# design.net
KiCad netlist of a schematic drawn in Altium Designer
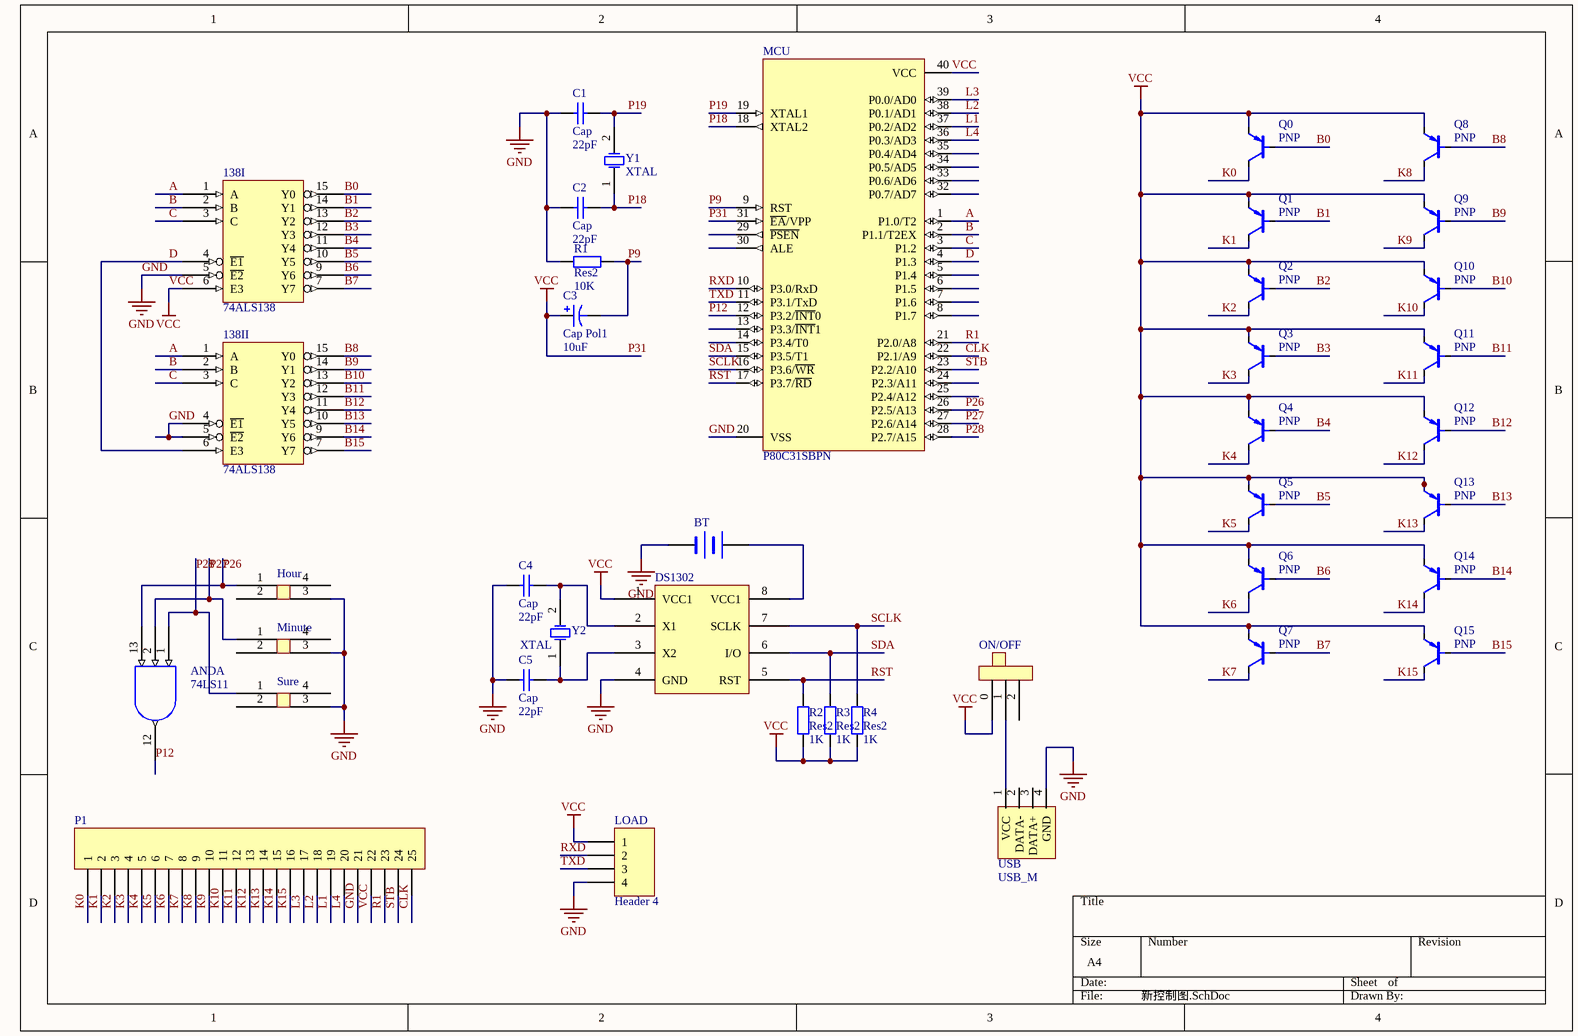
[diagram p0: 新控制图.SchDoc]

(export (version "E")
  (design (tool "Eeschema 10.0.6"))
  (components
    (comp (ref "138I")
      (value "74ALS138")
      (footprint "DIP-16")
      (libsource (lib "TTL74系列IC") (part "74ALS138"))
    )
    (comp (ref "138II")
      (value "74ALS138")
      (footprint "DIP-16")
      (libsource (lib "TTL74系列IC") (part "74ALS138"))
    )
    (comp (ref "AND") (value "74LS11") (footprint "DIP-14") (libsource (lib "TTL74系列IC") (part "74LS11")))
    (comp (ref "BT")
      (value "~")
      (footprint "纽扣电池:PCBComponent_1")
      (description "Battery")
      (libsource (lib "电池及电源") (part "干电池"))
    )
    (comp (ref "C1")
      (value "Cap")
      (footprint "Miscellaneous Connectors:HDR1X2")
      (description "Capacitor")
      (fields (field (name "ALTIUM_VALUE") "22pF") (field (name "PUBLISHER") "Altium Limited"))
      (libsource (lib "Miscellaneous Devices") (part "Cap"))
    )
    (comp (ref "C2")
      (value "Cap")
      (footprint "Miscellaneous Connectors:HDR1X2")
      (description "Capacitor")
      (fields (field (name "ALTIUM_VALUE") "22pF") (field (name "PUBLISHER") "Altium Limited"))
      (libsource (lib "Miscellaneous Devices") (part "Cap"))
    )
    (comp (ref "C3")
      (value "Cap Pol1")
      (footprint "单片机最小系统:LED")
      (description "Polarized Capacitor (Radial)")
      (fields (field (name "ALTIUM_VALUE") "10uF") (field (name "PUBLISHER") "Altium Limited"))
      (libsource (lib "Miscellaneous Devices") (part "Cap Pol1"))
    )
    (comp (ref "C4")
      (value "Cap")
      (footprint "PIN2")
      (description "Capacitor")
      (fields (field (name "ALTIUM_VALUE") "22pF") (field (name "PUBLISHER") "Altium Limited"))
      (libsource (lib "Miscellaneous Devices") (part "Cap"))
    )
    (comp (ref "C5")
      (value "Cap")
      (footprint "PIN2")
      (description "Capacitor")
      (fields (field (name "ALTIUM_VALUE") "22pF") (field (name "PUBLISHER") "Altium Limited"))
      (libsource (lib "Miscellaneous Devices") (part "Cap"))
    )
    (comp (ref "DS1302") (value "~") (footprint "DIP8") (libsource (lib "DS1302") (part "Component_1")))
    (comp (ref "Hour")
      (value "~")
      (footprint "立式按键:PCBComponent_1")
      (libsource (lib "按键1") (part "Component_1"))
    )
    (comp (ref "LOAD")
      (value "Header 4")
      (footprint "HDR1X4")
      (description "Header, 4-Pin")
      (fields (field (name "PUBLISHER") "Altium Limited"))
      (libsource (lib "Miscellaneous Connectors") (part "Header 4"))
    )
    (comp (ref "MCU")
      (value "P80C31SBPN")
      (footprint "SOT129-1")
      (description "80C51 8-Bit Microcontroller Family: 128 B RAM, ROMless, 2.7 V-5.5 V, Low Power, High Speed")
      (fields (field (name "PUBLISHER") "Altium Limited"))
      (libsource (lib "Philips Microcontroller 8-Bit") (part "P80C31SBPN"))
    )
    (comp (ref "Minute")
      (value "~")
      (footprint "立式按键:PCBComponent_1")
      (libsource (lib "按键1") (part "Component_1"))
    )
    (comp (ref "ON/OFF")
      (value "~")
      (footprint "新开关:PCBComponent_1")
      (libsource (lib "新开关") (part "Component_1"))
    )
    (comp (ref "P1")
      (value "~")
      (footprint "HDR1X25")
      (description "Header, 25-Pin")
      (fields (field (name "PUBLISHER") "Altium Limited"))
      (libsource (lib "Miscellaneous Connectors") (part "Header 25"))
    )
    (comp (ref "Q0") (value "PNP") (footprint "TO-92") (libsource (lib "常用元件库") (part "PNP")))
    (comp (ref "Q1") (value "PNP") (footprint "TO-92") (libsource (lib "常用元件库") (part "PNP")))
    (comp (ref "Q2") (value "PNP") (footprint "TO-92") (libsource (lib "常用元件库") (part "PNP")))
    (comp (ref "Q3") (value "PNP") (footprint "TO-92") (libsource (lib "常用元件库") (part "PNP")))
    (comp (ref "Q4") (value "PNP") (footprint "TO-92") (libsource (lib "常用元件库") (part "PNP")))
    (comp (ref "Q5") (value "PNP") (footprint "TO-92") (libsource (lib "常用元件库") (part "PNP")))
    (comp (ref "Q6") (value "PNP") (footprint "TO-92") (libsource (lib "常用元件库") (part "PNP")))
    (comp (ref "Q7") (value "PNP") (footprint "TO-92") (libsource (lib "常用元件库") (part "PNP")))
    (comp (ref "Q8") (value "PNP") (footprint "TO-92") (libsource (lib "常用元件库") (part "PNP")))
    (comp (ref "Q9") (value "PNP") (footprint "TO-92") (libsource (lib "常用元件库") (part "PNP")))
    (comp (ref "Q10") (value "PNP") (footprint "TO-92") (libsource (lib "常用元件库") (part "PNP")))
    (comp (ref "Q11") (value "PNP") (footprint "TO-92") (libsource (lib "常用元件库") (part "PNP")))
    (comp (ref "Q12") (value "PNP") (footprint "TO-92") (libsource (lib "常用元件库") (part "PNP")))
    (comp (ref "Q13") (value "PNP") (footprint "TO-92") (libsource (lib "常用元件库") (part "PNP")))
    (comp (ref "Q14") (value "PNP") (footprint "TO-92") (libsource (lib "常用元件库") (part "PNP")))
    (comp (ref "Q15") (value "PNP") (footprint "TO-92") (libsource (lib "常用元件库") (part "PNP")))
    (comp (ref "R1")
      (value "Res2")
      (footprint "AXIAL-0.4")
      (description "Resistor")
      (fields (field (name "ALTIUM_VALUE") "10K") (field (name "PUBLISHER") "Altium Limited"))
      (libsource (lib "Miscellaneous Devices") (part "Res2"))
    )
    (comp (ref "R2")
      (value "Res2")
      (footprint "AXIAL-0.4")
      (description "Resistor")
      (fields (field (name "ALTIUM_VALUE") "1K") (field (name "PUBLISHER") "Altium Limited"))
      (libsource (lib "") (part "Res2_1"))
    )
    (comp (ref "R3")
      (value "Res2")
      (footprint "AXIAL-0.4")
      (description "Resistor")
      (fields (field (name "ALTIUM_VALUE") "1K") (field (name "PUBLISHER") "Altium Limited"))
      (libsource (lib "") (part "Res2_1"))
    )
    (comp (ref "R4")
      (value "Res2")
      (footprint "AXIAL-0.4")
      (description "Resistor")
      (fields (field (name "ALTIUM_VALUE") "1K") (field (name "PUBLISHER") "Altium Limited"))
      (libsource (lib "") (part "Res2_1"))
    )
    (comp (ref "Sure")
      (value "~")
      (footprint "立式按键:PCBComponent_1")
      (libsource (lib "按键1") (part "Component_1"))
    )
    (comp (ref "USB") (value "USB_M") (footprint "USB") (libsource (lib "SCH封装库") (part "USB_M")))
    (comp (ref "Y1")
      (value "XTAL")
      (footprint "晶振:PCBComponent_1")
      (description "Crystal Oscillator")
      (fields (field (name "PUBLISHER") "Altium Limited"))
      (libsource (lib "Miscellaneous Devices") (part "XTAL"))
    )
    (comp (ref "Y2")
      (value "XTAL")
      (footprint "HDR1X2")
      (description "Crystal Oscillator")
      (fields (field (name "PUBLISHER") "Altium Limited"))
      (libsource (lib "Miscellaneous Devices") (part "XTAL"))
    )
  )
  (nets
    (net (code "1") (name "/A") (class "Default")
      (node (ref "138I") (pin "1") (pinfunction "A_1") (pintype "input"))
      (node (ref "138II") (pin "1") (pinfunction "A_1") (pintype "input"))
      (node (ref "MCU") (pin "1") (pinfunction "P1.0/T2_1") (pintype "bidirectional"))
    )
    (net (code "2") (name "/B") (class "Default")
      (node (ref "138I") (pin "2") (pinfunction "B_2") (pintype "input"))
      (node (ref "138II") (pin "2") (pinfunction "B_2") (pintype "input"))
      (node (ref "MCU") (pin "2") (pinfunction "P1.1/T2EX_2") (pintype "bidirectional"))
    )
    (net (code "3") (name "/B0") (class "Default")
      (node (ref "138I") (pin "15") (pinfunction "Y0_15") (pintype "output"))
      (node (ref "Q0") (pin "B") (pinfunction "b_B") (pintype "passive"))
    )
    (net (code "4") (name "/B1") (class "Default")
      (node (ref "138I") (pin "14") (pinfunction "Y1_14") (pintype "output"))
      (node (ref "Q1") (pin "B") (pinfunction "b_B") (pintype "passive"))
    )
    (net (code "5") (name "/B2") (class "Default")
      (node (ref "138I") (pin "13") (pinfunction "Y2_13") (pintype "output"))
      (node (ref "Q2") (pin "B") (pinfunction "b_B") (pintype "passive"))
    )
    (net (code "6") (name "/B3") (class "Default")
      (node (ref "138I") (pin "12") (pinfunction "Y3_12") (pintype "output"))
      (node (ref "Q3") (pin "B") (pinfunction "b_B") (pintype "passive"))
    )
    (net (code "7") (name "/B4") (class "Default")
      (node (ref "138I") (pin "11") (pinfunction "Y4_11") (pintype "output"))
      (node (ref "Q4") (pin "B") (pinfunction "b_B") (pintype "passive"))
    )
    (net (code "8") (name "/B5") (class "Default")
      (node (ref "138I") (pin "10") (pinfunction "Y5_10") (pintype "output"))
      (node (ref "Q5") (pin "B") (pinfunction "b_B") (pintype "passive"))
    )
    (net (code "9") (name "/B6") (class "Default")
      (node (ref "138I") (pin "9") (pinfunction "Y6_9") (pintype "output"))
      (node (ref "Q6") (pin "B") (pinfunction "b_B") (pintype "passive"))
    )
    (net (code "10") (name "/B7") (class "Default")
      (node (ref "138I") (pin "7") (pinfunction "Y7_7") (pintype "output"))
      (node (ref "Q7") (pin "B") (pinfunction "b_B") (pintype "passive"))
    )
    (net (code "11") (name "/B8") (class "Default")
      (node (ref "138II") (pin "15") (pinfunction "Y0_15") (pintype "output"))
      (node (ref "Q8") (pin "B") (pinfunction "b_B") (pintype "passive"))
    )
    (net (code "12") (name "/B9") (class "Default")
      (node (ref "138II") (pin "14") (pinfunction "Y1_14") (pintype "output"))
      (node (ref "Q9") (pin "B") (pinfunction "b_B") (pintype "passive"))
    )
    (net (code "13") (name "/B10") (class "Default")
      (node (ref "138II") (pin "13") (pinfunction "Y2_13") (pintype "output"))
      (node (ref "Q10") (pin "B") (pinfunction "b_B") (pintype "passive"))
    )
    (net (code "14") (name "/B11") (class "Default")
      (node (ref "138II") (pin "12") (pinfunction "Y3_12") (pintype "output"))
      (node (ref "Q11") (pin "B") (pinfunction "b_B") (pintype "passive"))
    )
    (net (code "15") (name "/B12") (class "Default")
      (node (ref "138II") (pin "11") (pinfunction "Y4_11") (pintype "output"))
      (node (ref "Q12") (pin "B") (pinfunction "b_B") (pintype "passive"))
    )
    (net (code "16") (name "/B13") (class "Default")
      (node (ref "138II") (pin "10") (pinfunction "Y5_10") (pintype "output"))
      (node (ref "Q13") (pin "B") (pinfunction "b_B") (pintype "passive"))
    )
    (net (code "17") (name "/B14") (class "Default")
      (node (ref "138II") (pin "9") (pinfunction "Y6_9") (pintype "output"))
      (node (ref "Q14") (pin "B") (pinfunction "b_B") (pintype "passive"))
    )
    (net (code "18") (name "/B15") (class "Default")
      (node (ref "138II") (pin "7") (pinfunction "Y7_7") (pintype "output"))
      (node (ref "Q15") (pin "B") (pinfunction "b_B") (pintype "passive"))
    )
    (net (code "19") (name "/C") (class "Default")
      (node (ref "138I") (pin "3") (pinfunction "C_3") (pintype "input"))
      (node (ref "138II") (pin "3") (pinfunction "C_3") (pintype "input"))
      (node (ref "MCU") (pin "3") (pinfunction "P1.2_3") (pintype "bidirectional"))
    )
    (net (code "20") (name "/CLK") (class "Default")
      (node (ref "MCU") (pin "22") (pinfunction "P2.1/A9_22") (pintype "bidirectional"))
      (node (ref "P1") (pin "25") (pinfunction "25_25") (pintype "passive"))
    )
    (net (code "21") (name "/D") (class "Default")
      (node (ref "138I") (pin "4") (pinfunction "~{E1}_4") (pintype "input"))
      (node (ref "138II") (pin "6") (pinfunction "E3_6") (pintype "input"))
      (node (ref "MCU") (pin "4") (pinfunction "P1.3_4") (pintype "bidirectional"))
    )
    (net (code "22") (name "/K0") (class "Default")
      (node (ref "P1") (pin "1") (pinfunction "1_1") (pintype "passive"))
      (node (ref "Q0") (pin "C") (pinfunction "c_C") (pintype "passive"))
    )
    (net (code "23") (name "/K1") (class "Default")
      (node (ref "P1") (pin "2") (pinfunction "2_2") (pintype "passive"))
      (node (ref "Q1") (pin "C") (pinfunction "c_C") (pintype "passive"))
    )
    (net (code "24") (name "/K2") (class "Default")
      (node (ref "P1") (pin "3") (pinfunction "3_3") (pintype "passive"))
      (node (ref "Q2") (pin "C") (pinfunction "c_C") (pintype "passive"))
    )
    (net (code "25") (name "/K3") (class "Default")
      (node (ref "P1") (pin "4") (pinfunction "4_4") (pintype "passive"))
      (node (ref "Q3") (pin "C") (pinfunction "c_C") (pintype "passive"))
    )
    (net (code "26") (name "/K4") (class "Default")
      (node (ref "P1") (pin "5") (pinfunction "5_5") (pintype "passive"))
      (node (ref "Q4") (pin "C") (pinfunction "c_C") (pintype "passive"))
    )
    (net (code "27") (name "/K5") (class "Default")
      (node (ref "P1") (pin "6") (pinfunction "6_6") (pintype "passive"))
      (node (ref "Q5") (pin "C") (pinfunction "c_C") (pintype "passive"))
    )
    (net (code "28") (name "/K6") (class "Default")
      (node (ref "P1") (pin "7") (pinfunction "7_7") (pintype "passive"))
      (node (ref "Q6") (pin "C") (pinfunction "c_C") (pintype "passive"))
    )
    (net (code "29") (name "/K7") (class "Default")
      (node (ref "P1") (pin "8") (pinfunction "8_8") (pintype "passive"))
      (node (ref "Q7") (pin "C") (pinfunction "c_C") (pintype "passive"))
    )
    (net (code "30") (name "/K8") (class "Default")
      (node (ref "P1") (pin "9") (pinfunction "9_9") (pintype "passive"))
      (node (ref "Q8") (pin "C") (pinfunction "c_C") (pintype "passive"))
    )
    (net (code "31") (name "/K9") (class "Default")
      (node (ref "P1") (pin "10") (pinfunction "10_10") (pintype "passive"))
      (node (ref "Q9") (pin "C") (pinfunction "c_C") (pintype "passive"))
    )
    (net (code "32") (name "/K10") (class "Default")
      (node (ref "P1") (pin "11") (pinfunction "11_11") (pintype "passive"))
      (node (ref "Q10") (pin "C") (pinfunction "c_C") (pintype "passive"))
    )
    (net (code "33") (name "/K11") (class "Default")
      (node (ref "P1") (pin "12") (pinfunction "12_12") (pintype "passive"))
      (node (ref "Q11") (pin "C") (pinfunction "c_C") (pintype "passive"))
    )
    (net (code "34") (name "/K12") (class "Default")
      (node (ref "P1") (pin "13") (pinfunction "13_13") (pintype "passive"))
      (node (ref "Q12") (pin "C") (pinfunction "c_C") (pintype "passive"))
    )
    (net (code "35") (name "/K13") (class "Default")
      (node (ref "P1") (pin "14") (pinfunction "14_14") (pintype "passive"))
      (node (ref "Q13") (pin "C") (pinfunction "c_C") (pintype "passive"))
    )
    (net (code "36") (name "/K14") (class "Default")
      (node (ref "P1") (pin "15") (pinfunction "15_15") (pintype "passive"))
      (node (ref "Q14") (pin "C") (pinfunction "c_C") (pintype "passive"))
    )
    (net (code "37") (name "/K15") (class "Default")
      (node (ref "P1") (pin "16") (pinfunction "16_16") (pintype "passive"))
      (node (ref "Q15") (pin "C") (pinfunction "c_C") (pintype "passive"))
    )
    (net (code "38") (name "/L1") (class "Default")
      (node (ref "MCU") (pin "37") (pinfunction "P0.2/AD2_37") (pintype "bidirectional"))
      (node (ref "P1") (pin "19") (pinfunction "19_19") (pintype "passive"))
    )
    (net (code "39") (name "/L2") (class "Default")
      (node (ref "MCU") (pin "38") (pinfunction "P0.1/AD1_38") (pintype "bidirectional"))
      (node (ref "P1") (pin "18") (pinfunction "18_18") (pintype "passive"))
    )
    (net (code "40") (name "/L3") (class "Default")
      (node (ref "MCU") (pin "39") (pinfunction "P0.0/AD0_39") (pintype "bidirectional"))
      (node (ref "P1") (pin "17") (pinfunction "17_17") (pintype "passive"))
    )
    (net (code "41") (name "/L4") (class "Default")
      (node (ref "MCU") (pin "36") (pinfunction "P0.3/AD3_36") (pintype "bidirectional"))
      (node (ref "P1") (pin "20") (pinfunction "20_20") (pintype "passive"))
    )
    (net (code "42") (name "/P9") (class "Default")
      (node (ref "C3") (pin "2") (pinfunction "2_2") (pintype "passive"))
      (node (ref "MCU") (pin "9") (pinfunction "RST_9") (pintype "input"))
      (node (ref "R1") (pin "2") (pinfunction "2_2") (pintype "passive"))
    )
    (net (code "43") (name "/P12") (class "Default")
      (node (ref "AND") (pin "12") (pintype "output"))
      (node (ref "MCU") (pin "12") (pinfunction "P3.2/~{INT}0_12") (pintype "bidirectional"))
    )
    (net (code "44") (name "/P18") (class "Default")
      (node (ref "C2") (pin "2") (pinfunction "2_2") (pintype "passive"))
      (node (ref "MCU") (pin "18") (pinfunction "XTAL2_18") (pintype "output"))
      (node (ref "Y1") (pin "1") (pinfunction "OSC1_1") (pintype "passive"))
    )
    (net (code "45") (name "/P19") (class "Default")
      (node (ref "C1") (pin "2") (pinfunction "2_2") (pintype "passive"))
      (node (ref "MCU") (pin "19") (pinfunction "XTAL1_19") (pintype "input"))
      (node (ref "Y1") (pin "2") (pinfunction "OSC2_2") (pintype "passive"))
    )
    (net (code "46") (name "/P26") (class "Default")
      (node (ref "AND") (pin "13") (pintype "input"))
      (node (ref "Hour") (pin "1") (pintype "passive"))
      (node (ref "MCU") (pin "26") (pinfunction "P2.5/A13_26") (pintype "bidirectional"))
    )
    (net (code "47") (name "/P27") (class "Default")
      (node (ref "AND") (pin "2") (pintype "input"))
      (node (ref "MCU") (pin "27") (pinfunction "P2.6/A14_27") (pintype "bidirectional"))
      (node (ref "Minute") (pin "1") (pintype "passive"))
    )
    (net (code "48") (name "/P28") (class "Default")
      (node (ref "AND") (pin "1") (pintype "input"))
      (node (ref "MCU") (pin "28") (pinfunction "P2.7/A15_28") (pintype "bidirectional"))
      (node (ref "Sure") (pin "1") (pintype "passive"))
    )
    (net (code "49") (name "/R1") (class "Default")
      (node (ref "MCU") (pin "21") (pinfunction "P2.0/A8_21") (pintype "bidirectional"))
      (node (ref "P1") (pin "23") (pinfunction "23_23") (pintype "passive"))
    )
    (net (code "50") (name "/RST") (class "Default")
      (node (ref "DS1302") (pin "5") (pinfunction "RST_5") (pintype "passive"))
      (node (ref "MCU") (pin "17") (pinfunction "P3.7/~{RD}_17") (pintype "bidirectional"))
      (node (ref "R2") (pin "2") (pinfunction "2_2") (pintype "passive"))
    )
    (net (code "51") (name "/RXD") (class "Default")
      (node (ref "LOAD") (pin "2") (pinfunction "2_2") (pintype "passive"))
      (node (ref "MCU") (pin "10") (pinfunction "P3.0/RxD_10") (pintype "bidirectional"))
    )
    (net (code "52") (name "/SCLK") (class "Default")
      (node (ref "DS1302") (pin "7") (pinfunction "SCLK_7") (pintype "passive"))
      (node (ref "MCU") (pin "16") (pinfunction "P3.6/~{WR}_16") (pintype "bidirectional"))
      (node (ref "R4") (pin "2") (pinfunction "2_2") (pintype "passive"))
    )
    (net (code "53") (name "/SDA") (class "Default")
      (node (ref "DS1302") (pin "6") (pinfunction "I/O_6") (pintype "passive"))
      (node (ref "MCU") (pin "15") (pinfunction "P3.5/T1_15") (pintype "bidirectional"))
      (node (ref "R3") (pin "2") (pinfunction "2_2") (pintype "passive"))
    )
    (net (code "54") (name "/STB") (class "Default")
      (node (ref "MCU") (pin "23") (pinfunction "P2.2/A10_23") (pintype "bidirectional"))
      (node (ref "P1") (pin "24") (pinfunction "24_24") (pintype "passive"))
    )
    (net (code "55") (name "/TXD") (class "Default")
      (node (ref "LOAD") (pin "3") (pinfunction "3_3") (pintype "passive"))
      (node (ref "MCU") (pin "11") (pinfunction "P3.1/TxD_11") (pintype "bidirectional"))
    )
    (net (code "56") (name "GND") (class "Default")
      (node (ref "138I") (pin "5") (pinfunction "~{E2}_5") (pintype "input"))
      (node (ref "138I") (pin "8") (pinfunction "GND_8") (pintype "power_in"))
      (node (ref "138II") (pin "4") (pinfunction "~{E1}_4") (pintype "input"))
      (node (ref "138II") (pin "5") (pinfunction "~{E2}_5") (pintype "input"))
      (node (ref "138II") (pin "8") (pinfunction "GND_8") (pintype "power_in"))
      (node (ref "AND") (pin "7") (pinfunction "GND_7") (pintype "power_in"))
      (node (ref "BT") (pin "2") (pinfunction "-_2") (pintype "passive"))
      (node (ref "C1") (pin "1") (pinfunction "1_1") (pintype "passive"))
      (node (ref "C2") (pin "1") (pinfunction "1_1") (pintype "passive"))
      (node (ref "C4") (pin "1") (pinfunction "1_1") (pintype "passive"))
      (node (ref "C5") (pin "1") (pinfunction "1_1") (pintype "passive"))
      (node (ref "DS1302") (pin "4") (pinfunction "GND_4") (pintype "passive"))
      (node (ref "Hour") (pin "3") (pintype "passive"))
      (node (ref "LOAD") (pin "4") (pinfunction "4_4") (pintype "passive"))
      (node (ref "MCU") (pin "20") (pinfunction "VSS_20") (pintype "power_in"))
      (node (ref "Minute") (pin "3") (pintype "passive"))
      (node (ref "P1") (pin "21") (pinfunction "21_21") (pintype "passive"))
      (node (ref "R1") (pin "1") (pinfunction "1_1") (pintype "passive"))
      (node (ref "Sure") (pin "3") (pintype "passive"))
      (node (ref "USB") (pin "4") (pinfunction "GND_4") (pintype "passive"))
    )
    (net (code "57") (name "Net-(BT-+)") (class "Default")
      (node (ref "BT") (pin "1") (pinfunction "+_1") (pintype "passive"))
      (node (ref "DS1302") (pin "8") (pinfunction "VCC1_8") (pintype "passive"))
    )
    (net (code "58") (name "Net-(DS1302-X1)") (class "Default")
      (node (ref "C4") (pin "2") (pinfunction "2_2") (pintype "passive"))
      (node (ref "DS1302") (pin "2") (pinfunction "X1_2") (pintype "passive"))
      (node (ref "Y2") (pin "2") (pinfunction "OSC2_2") (pintype "passive"))
    )
    (net (code "59") (name "Net-(DS1302-X2)") (class "Default")
      (node (ref "C5") (pin "2") (pinfunction "2_2") (pintype "passive"))
      (node (ref "DS1302") (pin "3") (pinfunction "X2_3") (pintype "passive"))
      (node (ref "Y2") (pin "1") (pinfunction "OSC1_1") (pintype "passive"))
    )
    (net (code "60") (name "Net-(USB-VCC)") (class "Default")
      (node (ref "ON/OFF") (pin "1") (pintype "passive"))
      (node (ref "USB") (pin "1") (pinfunction "VCC_1") (pintype "passive"))
    )
    (net (code "61") (name "VCC") (class "Default")
      (node (ref "138I") (pin "16") (pinfunction "VCC_16") (pintype "power_in"))
      (node (ref "138I") (pin "6") (pinfunction "E3_6") (pintype "input"))
      (node (ref "138II") (pin "16") (pinfunction "VCC_16") (pintype "power_in"))
      (node (ref "AND") (pin "14") (pinfunction "VCC_14") (pintype "power_in"))
      (node (ref "C3") (pin "1") (pinfunction "1_1") (pintype "passive"))
      (node (ref "DS1302") (pin "1") (pinfunction "VCC1_1") (pintype "passive"))
      (node (ref "LOAD") (pin "1") (pinfunction "1_1") (pintype "passive"))
      (node (ref "MCU") (pin "31") (pinfunction "~{EA}/VPP_31") (pintype "input"))
      (node (ref "MCU") (pin "40") (pinfunction "VCC_40") (pintype "power_in"))
      (node (ref "ON/OFF") (pin "0") (pintype "passive"))
      (node (ref "P1") (pin "22") (pinfunction "22_22") (pintype "passive"))
      (node (ref "Q0") (pin "E") (pinfunction "e_E") (pintype "passive"))
      (node (ref "Q1") (pin "E") (pinfunction "e_E") (pintype "passive"))
      (node (ref "Q10") (pin "E") (pinfunction "e_E") (pintype "passive"))
      (node (ref "Q11") (pin "E") (pinfunction "e_E") (pintype "passive"))
      (node (ref "Q12") (pin "E") (pinfunction "e_E") (pintype "passive"))
      (node (ref "Q13") (pin "E") (pinfunction "e_E") (pintype "passive"))
      (node (ref "Q14") (pin "E") (pinfunction "e_E") (pintype "passive"))
      (node (ref "Q15") (pin "E") (pinfunction "e_E") (pintype "passive"))
      (node (ref "Q2") (pin "E") (pinfunction "e_E") (pintype "passive"))
      (node (ref "Q3") (pin "E") (pinfunction "e_E") (pintype "passive"))
      (node (ref "Q4") (pin "E") (pinfunction "e_E") (pintype "passive"))
      (node (ref "Q5") (pin "E") (pinfunction "e_E") (pintype "passive"))
      (node (ref "Q6") (pin "E") (pinfunction "e_E") (pintype "passive"))
      (node (ref "Q7") (pin "E") (pinfunction "e_E") (pintype "passive"))
      (node (ref "Q8") (pin "E") (pinfunction "e_E") (pintype "passive"))
      (node (ref "Q9") (pin "E") (pinfunction "e_E") (pintype "passive"))
      (node (ref "R2") (pin "1") (pinfunction "1_1") (pintype "passive"))
      (node (ref "R3") (pin "1") (pinfunction "1_1") (pintype "passive"))
      (node (ref "R4") (pin "1") (pinfunction "1_1") (pintype "passive"))
    )
    (net (code "62") (name "unconnected-(Hour-Pad2)") (class "Default")
      (node (ref "Hour") (pin "2") (pintype "passive"))
    )
    (net (code "63") (name "unconnected-(Hour-Pad4)") (class "Default")
      (node (ref "Hour") (pin "4") (pintype "passive"))
    )
    (net (code "64") (name "unconnected-(MCU-ALE-Pad30)") (class "Default")
      (node (ref "MCU") (pin "30") (pinfunction "ALE_30") (pintype "output"))
    )
    (net (code "65") (name "unconnected-(MCU-P0.4{slash}AD4-Pad35)") (class "Default")
      (node (ref "MCU") (pin "35") (pinfunction "P0.4/AD4_35") (pintype "bidirectional"))
    )
    (net (code "66") (name "unconnected-(MCU-P0.5{slash}AD5-Pad34)") (class "Default")
      (node (ref "MCU") (pin "34") (pinfunction "P0.5/AD5_34") (pintype "bidirectional"))
    )
    (net (code "67") (name "unconnected-(MCU-P0.6{slash}AD6-Pad33)") (class "Default")
      (node (ref "MCU") (pin "33") (pinfunction "P0.6/AD6_33") (pintype "bidirectional"))
    )
    (net (code "68") (name "unconnected-(MCU-P0.7{slash}AD7-Pad32)") (class "Default")
      (node (ref "MCU") (pin "32") (pinfunction "P0.7/AD7_32") (pintype "bidirectional"))
    )
    (net (code "69") (name "unconnected-(MCU-P1.4-Pad5)") (class "Default")
      (node (ref "MCU") (pin "5") (pinfunction "P1.4_5") (pintype "bidirectional"))
    )
    (net (code "70") (name "unconnected-(MCU-P1.5-Pad6)") (class "Default")
      (node (ref "MCU") (pin "6") (pinfunction "P1.5_6") (pintype "bidirectional"))
    )
    (net (code "71") (name "unconnected-(MCU-P1.6-Pad7)") (class "Default")
      (node (ref "MCU") (pin "7") (pinfunction "P1.6_7") (pintype "bidirectional"))
    )
    (net (code "72") (name "unconnected-(MCU-P1.7-Pad8)") (class "Default")
      (node (ref "MCU") (pin "8") (pinfunction "P1.7_8") (pintype "bidirectional"))
    )
    (net (code "73") (name "unconnected-(MCU-P2.3{slash}A11-Pad24)") (class "Default")
      (node (ref "MCU") (pin "24") (pinfunction "P2.3/A11_24") (pintype "bidirectional"))
    )
    (net (code "74") (name "unconnected-(MCU-P2.4{slash}A12-Pad25)") (class "Default")
      (node (ref "MCU") (pin "25") (pinfunction "P2.4/A12_25") (pintype "bidirectional"))
    )
    (net (code "75") (name "unconnected-(MCU-P3.3{slash}~{INT}1-Pad13)") (class "Default")
      (node (ref "MCU") (pin "13") (pinfunction "P3.3/~{INT}1_13") (pintype "bidirectional"))
    )
    (net (code "76") (name "unconnected-(MCU-P3.4{slash}T0-Pad14)") (class "Default")
      (node (ref "MCU") (pin "14") (pinfunction "P3.4/T0_14") (pintype "bidirectional"))
    )
    (net (code "77") (name "unconnected-(MCU-~{PSEN}-Pad29)") (class "Default")
      (node (ref "MCU") (pin "29") (pinfunction "~{PSEN}_29") (pintype "output"))
    )
    (net (code "78") (name "unconnected-(Minute-Pad2)") (class "Default")
      (node (ref "Minute") (pin "2") (pintype "passive"))
    )
    (net (code "79") (name "unconnected-(Minute-Pad4)") (class "Default")
      (node (ref "Minute") (pin "4") (pintype "passive"))
    )
    (net (code "80") (name "unconnected-(ON/OFF-Pad2)") (class "Default")
      (node (ref "ON/OFF") (pin "2") (pintype "passive"))
    )
    (net (code "81") (name "unconnected-(Sure-Pad2)") (class "Default")
      (node (ref "Sure") (pin "2") (pintype "passive"))
    )
    (net (code "82") (name "unconnected-(Sure-Pad4)") (class "Default")
      (node (ref "Sure") (pin "4") (pintype "passive"))
    )
    (net (code "83") (name "unconnected-(USB-DATA+-Pad3)") (class "Default")
      (node (ref "USB") (pin "3") (pinfunction "DATA+_3") (pintype "passive"))
    )
    (net (code "84") (name "unconnected-(USB-DATA--Pad2)") (class "Default")
      (node (ref "USB") (pin "2") (pinfunction "DATA-_2") (pintype "passive"))
    )
  )
)
